# 02_IO.net
KiCad netlist of a schematic drawn in Altium Designer
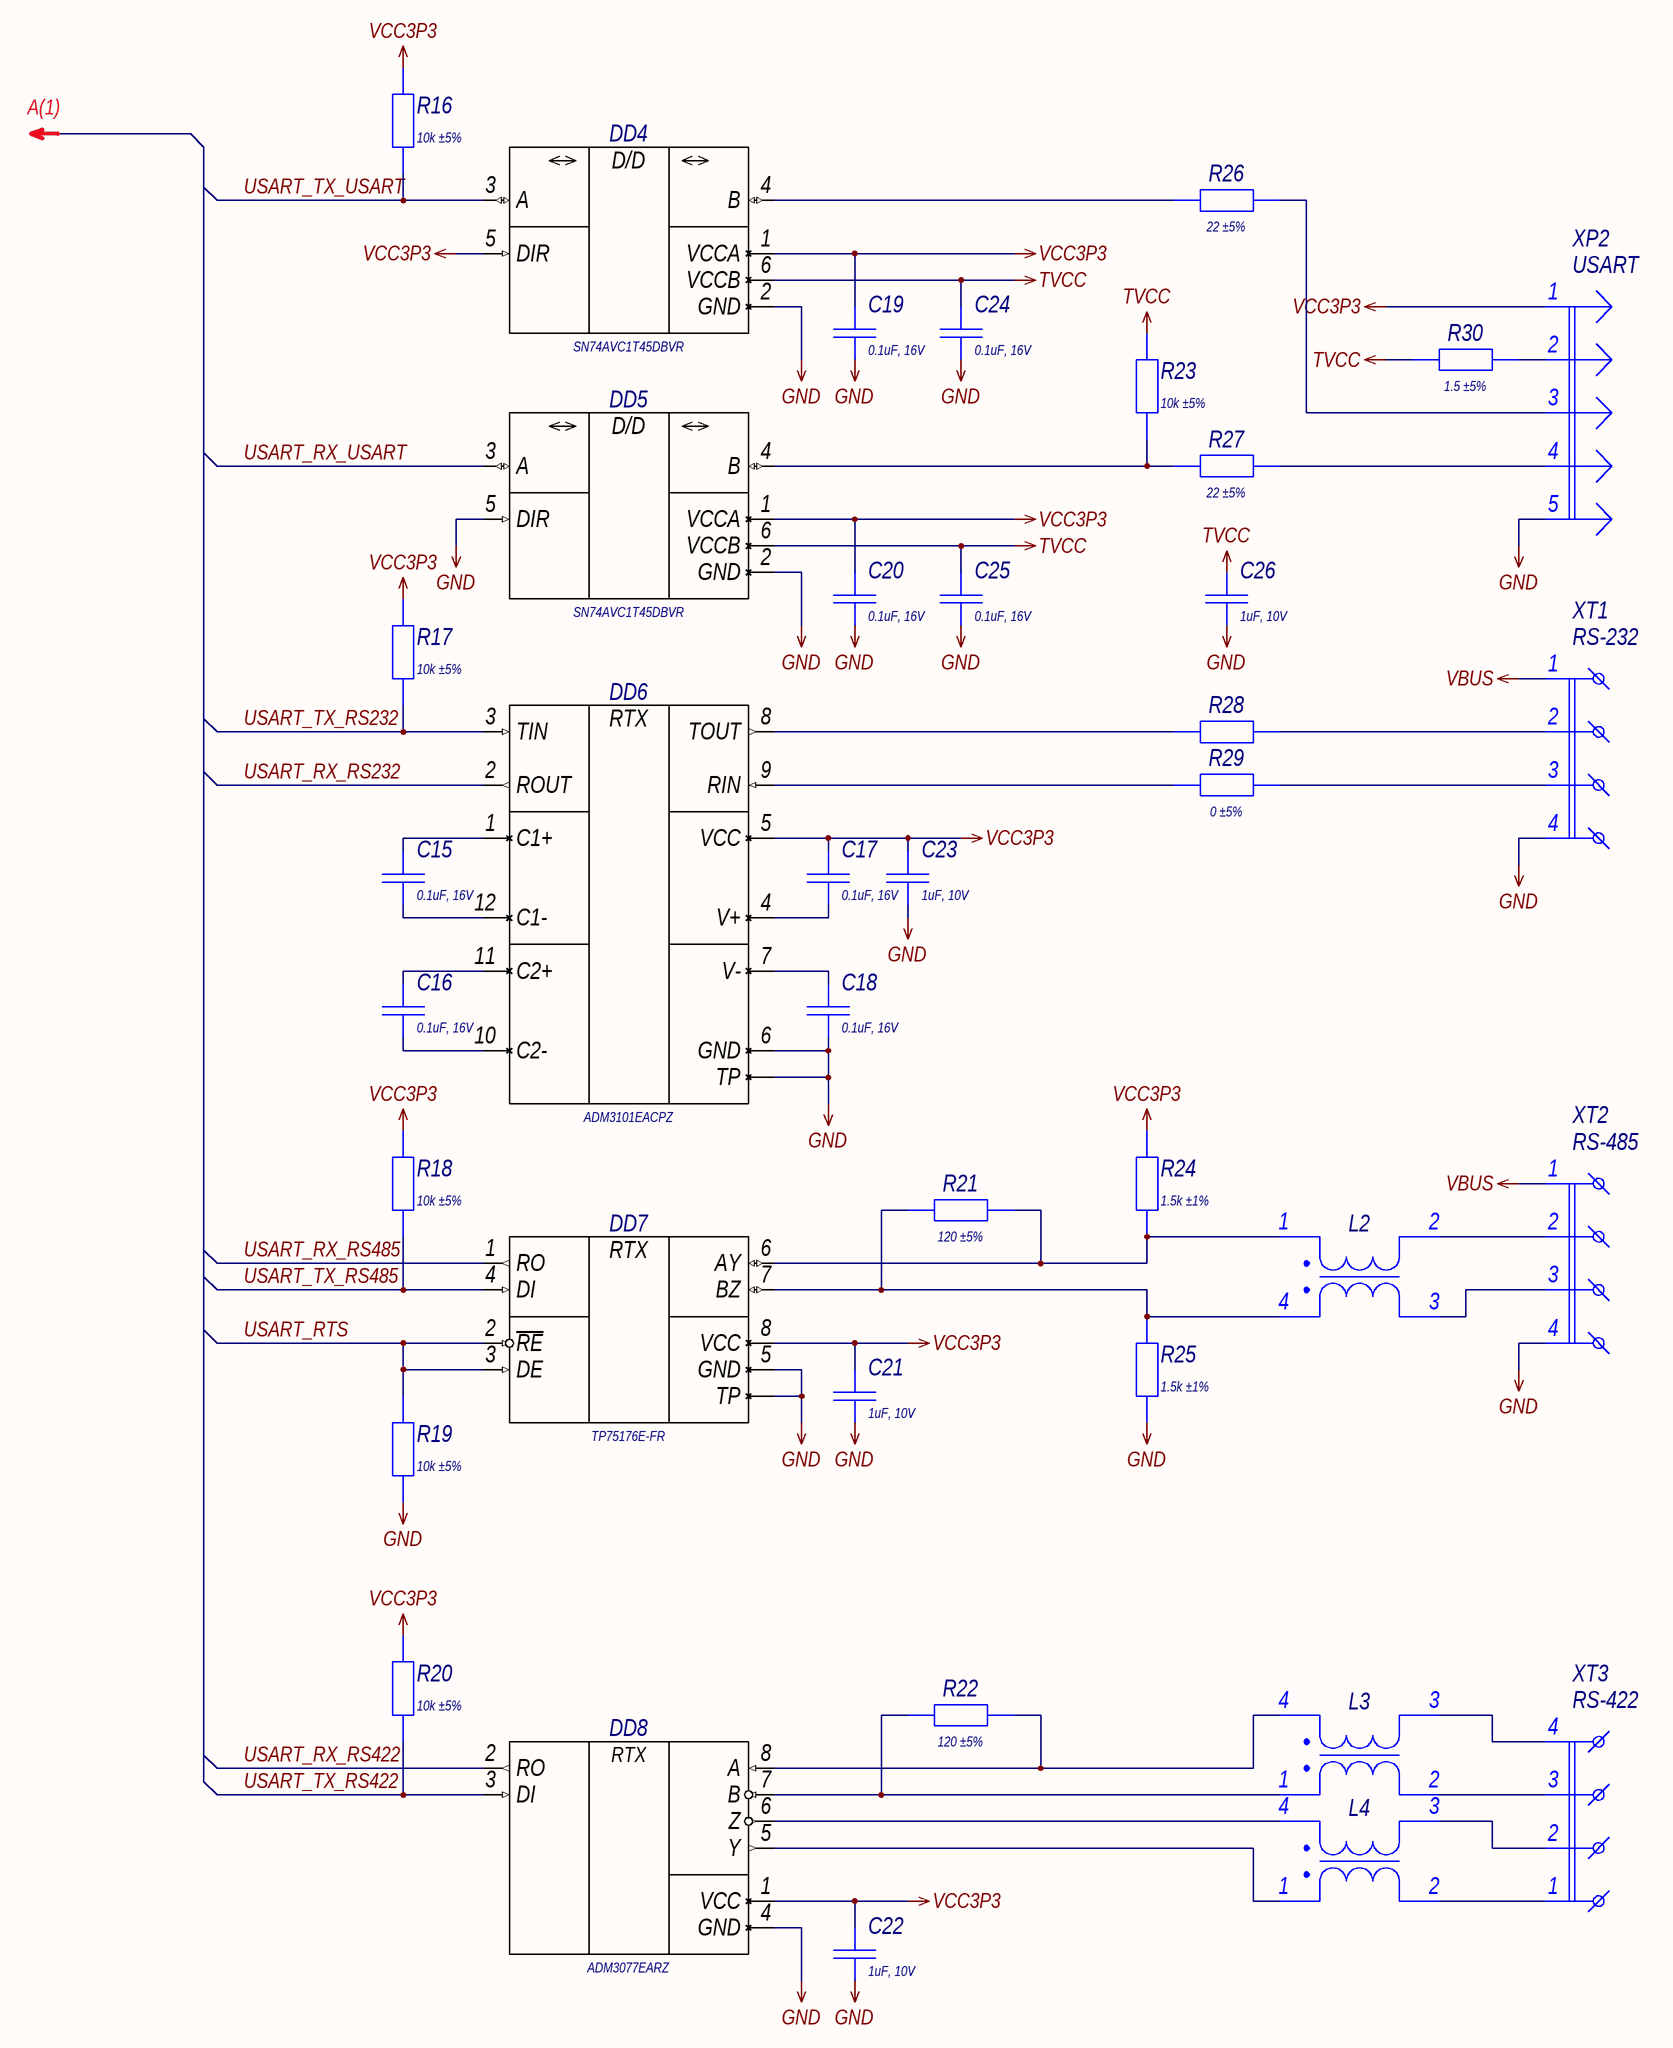
[diagram p0: 02_IO.SchDoc]

(export (version "E")
  (design (tool "Eeschema 10.0.6"))
  (components
    (comp (ref "C15")
      (value "Capacitor")
      (footprint "C0402_100X050H050_H")
      (fields
        (field (name "SCHEMATIC VALUE") "0.1uF, 16V")
        (field (name "PART NUMBER") "GCM155R71C104KA55D")
        (field (name "VOLTAGE") "16V")
        (field (name "TOLERANCE") "±10%")
        (field (name "PUBLISHER") "Andrew Danich")
      )
      (libsource (lib "ADLib") (part "Capacitor"))
    )
    (comp (ref "C16")
      (value "Capacitor")
      (footprint "C0402_100X050H050_H")
      (fields
        (field (name "SCHEMATIC VALUE") "0.1uF, 16V")
        (field (name "PART NUMBER") "GCM155R71C104KA55D")
        (field (name "VOLTAGE") "16V")
        (field (name "TOLERANCE") "±10%")
        (field (name "PUBLISHER") "Andrew Danich")
      )
      (libsource (lib "ADLib") (part "Capacitor"))
    )
    (comp (ref "C17")
      (value "Capacitor")
      (footprint "C0402_100X050H050_H")
      (fields
        (field (name "SCHEMATIC VALUE") "0.1uF, 16V")
        (field (name "PART NUMBER") "GCM155R71C104KA55D")
        (field (name "VOLTAGE") "16V")
        (field (name "TOLERANCE") "±10%")
        (field (name "PUBLISHER") "Andrew Danich")
      )
      (libsource (lib "ADLib") (part "Capacitor"))
    )
    (comp (ref "C18")
      (value "Capacitor")
      (footprint "C0402_100X050H050_H")
      (fields
        (field (name "SCHEMATIC VALUE") "0.1uF, 16V")
        (field (name "PART NUMBER") "GCM155R71C104KA55D")
        (field (name "VOLTAGE") "16V")
        (field (name "TOLERANCE") "±10%")
        (field (name "PUBLISHER") "Andrew Danich")
      )
      (libsource (lib "ADLib") (part "Capacitor"))
    )
    (comp (ref "C19")
      (value "Capacitor")
      (footprint "C0402_100X050H050_H")
      (fields
        (field (name "SCHEMATIC VALUE") "0.1uF, 16V")
        (field (name "PART NUMBER") "GCM155R71C104KA55D")
        (field (name "VOLTAGE") "16V")
        (field (name "TOLERANCE") "±10%")
        (field (name "PUBLISHER") "Andrew Danich")
      )
      (libsource (lib "ADLib") (part "Capacitor"))
    )
    (comp (ref "C20")
      (value "Capacitor")
      (footprint "C0402_100X050H050_H")
      (fields
        (field (name "SCHEMATIC VALUE") "0.1uF, 16V")
        (field (name "PART NUMBER") "GCM155R71C104KA55D")
        (field (name "VOLTAGE") "16V")
        (field (name "TOLERANCE") "±10%")
        (field (name "PUBLISHER") "Andrew Danich")
      )
      (libsource (lib "ADLib") (part "Capacitor"))
    )
    (comp (ref "C21")
      (value "Capacitor")
      (footprint "C0402_100X050H050_H")
      (fields
        (field (name "SCHEMATIC VALUE") "1uF, 10V")
        (field (name "PART NUMBER") "GRM155C71A105KE11D")
        (field (name "VOLTAGE") "10V")
        (field (name "TOLERANCE") "±10%")
        (field (name "PUBLISHER") "Andrew Danich")
      )
      (libsource (lib "ADLib") (part "Capacitor"))
    )
    (comp (ref "C22")
      (value "Capacitor")
      (footprint "C0402_100X050H050_H")
      (fields
        (field (name "SCHEMATIC VALUE") "1uF, 10V")
        (field (name "PART NUMBER") "GRM155C71A105KE11D")
        (field (name "VOLTAGE") "10V")
        (field (name "TOLERANCE") "±10%")
        (field (name "PUBLISHER") "Andrew Danich")
      )
      (libsource (lib "ADLib") (part "Capacitor"))
    )
    (comp (ref "C23")
      (value "Capacitor")
      (footprint "C0402_100X050H050_H")
      (fields
        (field (name "SCHEMATIC VALUE") "1uF, 10V")
        (field (name "PART NUMBER") "GRM155C71A105KE11D")
        (field (name "VOLTAGE") "10V")
        (field (name "TOLERANCE") "±10%")
        (field (name "PUBLISHER") "Andrew Danich")
      )
      (libsource (lib "ADLib") (part "Capacitor"))
    )
    (comp (ref "C24")
      (value "Capacitor")
      (footprint "C0402_100X050H050_H")
      (fields
        (field (name "SCHEMATIC VALUE") "0.1uF, 16V")
        (field (name "PART NUMBER") "GCM155R71C104KA55D")
        (field (name "VOLTAGE") "16V")
        (field (name "TOLERANCE") "±10%")
        (field (name "PUBLISHER") "Andrew Danich")
      )
      (libsource (lib "ADLib") (part "Capacitor"))
    )
    (comp (ref "C25")
      (value "Capacitor")
      (footprint "C0402_100X050H050_H")
      (fields
        (field (name "SCHEMATIC VALUE") "0.1uF, 16V")
        (field (name "PART NUMBER") "GCM155R71C104KA55D")
        (field (name "VOLTAGE") "16V")
        (field (name "TOLERANCE") "±10%")
        (field (name "PUBLISHER") "Andrew Danich")
      )
      (libsource (lib "ADLib") (part "Capacitor"))
    )
    (comp (ref "C26")
      (value "Capacitor")
      (footprint "C0402_100X050H050_H")
      (fields
        (field (name "SCHEMATIC VALUE") "1uF, 10V")
        (field (name "PART NUMBER") "GRM155C71A105KE11D")
        (field (name "VOLTAGE") "10V")
        (field (name "TOLERANCE") "±10%")
        (field (name "PUBLISHER") "Andrew Danich")
      )
      (libsource (lib "ADLib") (part "Capacitor"))
    )
    (comp (ref "DD4")
      (value "SN74AVC1T45Dx-Series")
      (footprint "SOT-23-6_095P290X160X145_N")
      (fields
        (field (name "SCHEMATIC VALUE") "SN74AVC1T45DBVR")
        (field (name "PART NUMBER") "SN74AVC1T45DBVR")
        (field (name "LCSC PART") "C131978")
        (field (name "MANUFACTURER") "Texas Instruments")
        (field (name "PUBLISHER") "Andrew Danich")
      )
      (libsource (lib "ADLib") (part "SN74AVC1T45Dx-Series"))
    )
    (comp (ref "DD5")
      (value "SN74AVC1T45Dx-Series")
      (footprint "SOT-23-6_095P290X160X145_N")
      (fields
        (field (name "SCHEMATIC VALUE") "SN74AVC1T45DBVR")
        (field (name "PART NUMBER") "SN74AVC1T45DBVR")
        (field (name "LCSC PART") "C131978")
        (field (name "MANUFACTURER") "Texas Instruments")
        (field (name "PUBLISHER") "Andrew Danich")
      )
      (libsource (lib "ADLib") (part "SN74AVC1T45Dx-Series"))
    )
    (comp (ref "DD6")
      (value "ADM3101EAC")
      (footprint "LFCSP-12_050P300X300X080_N")
      (fields
        (field (name "SCHEMATIC VALUE") "ADM3101EACPZ")
        (field (name "PART NUMBER") "ADM3101EACPZ")
        (field (name "MANUFACTURER") "Analog Devices")
        (field (name "PUBLISHER") "Andrew Danich")
      )
      (libsource (lib "ADLib") (part "ADM3101EAC"))
    )
    (comp (ref "DD7")
      (value "TP75176E-FR")
      (footprint "DFN-8_065P300X300X090_N")
      (fields
        (field (name "SCHEMATIC VALUE") "TP75176E-FR")
        (field (name "MANUFACTURER") "3PEAK")
        (field (name "PUBLISHER") "Andrew Danich")
      )
      (libsource (lib "ADLib") (part "TP75176E-FR"))
    )
    (comp (ref "DD8")
      (value "ADM3077")
      (footprint "SOIC-8_127P490X391X155_N")
      (fields
        (field (name "SCHEMATIC VALUE") "ADM3077EARZ")
        (field (name "PART NUMBER") "ADM3077EARZ")
        (field (name "MANUFACTURER") "Analog Devices")
        (field (name "PUBLISHER") "Andrew Danich")
      )
      (libsource (lib "ADLib") (part "ADM3077"))
    )
    (comp (ref "L2")
      (value "Coil-2xCommon_H")
      (footprint "DLW21HN-Series")
      (fields
        (field (name "PART NUMBER") "DLW21HN121SQ2L")
        (field (name "LCSC PART") "C113040")
        (field (name "MANUFACTURER") "Murata")
        (field (name "PUBLISHER") "Andrew Danich")
      )
      (libsource (lib "ADLib") (part "Coil-2xCommon_H"))
    )
    (comp (ref "L3")
      (value "Coil-2xCommon_H")
      (footprint "DLW21HN-Series")
      (fields
        (field (name "PART NUMBER") "DLW21HN121SQ2L")
        (field (name "LCSC PART") "C113040")
        (field (name "MANUFACTURER") "Murata")
        (field (name "PUBLISHER") "Andrew Danich")
      )
      (libsource (lib "") (part "Coil-2xCommon_H_1"))
    )
    (comp (ref "L4")
      (value "Coil-2xCommon_H")
      (footprint "DLW21HN-Series")
      (fields
        (field (name "PART NUMBER") "DLW21HN121SQ2L")
        (field (name "LCSC PART") "C113040")
        (field (name "MANUFACTURER") "Murata")
        (field (name "PUBLISHER") "Andrew Danich")
      )
      (libsource (lib "") (part "Coil-2xCommon_H_1"))
    )
    (comp (ref "R16")
      (value "Resistor")
      (footprint "R0402_100X050H035_H")
      (fields
        (field (name "SCHEMATIC VALUE") "10k ±5%")
        (field (name "PART NUMBER") "RC0402JR-0710KL")
        (field (name "TOLERANCE") "±5%")
        (field (name "MANUFACTURER") "Yageo")
        (field (name "PUBLISHER") "Andrew Danich")
      )
      (libsource (lib "ADLib") (part "Resistor"))
    )
    (comp (ref "R17")
      (value "Resistor")
      (footprint "R0402_100X050H035_H")
      (fields
        (field (name "SCHEMATIC VALUE") "10k ±5%")
        (field (name "PART NUMBER") "RC0402JR-0710KL")
        (field (name "TOLERANCE") "±5%")
        (field (name "MANUFACTURER") "Yageo")
        (field (name "PUBLISHER") "Andrew Danich")
      )
      (libsource (lib "ADLib") (part "Resistor"))
    )
    (comp (ref "R18")
      (value "Resistor")
      (footprint "R0402_100X050H035_H")
      (fields
        (field (name "SCHEMATIC VALUE") "10k ±5%")
        (field (name "PART NUMBER") "RC0402JR-0710KL")
        (field (name "TOLERANCE") "±5%")
        (field (name "MANUFACTURER") "Yageo")
        (field (name "PUBLISHER") "Andrew Danich")
      )
      (libsource (lib "ADLib") (part "Resistor"))
    )
    (comp (ref "R19")
      (value "Resistor")
      (footprint "R0402_100X050H035_H")
      (fields
        (field (name "SCHEMATIC VALUE") "10k ±5%")
        (field (name "PART NUMBER") "RC0402JR-0710KL")
        (field (name "TOLERANCE") "±5%")
        (field (name "MANUFACTURER") "Yageo")
        (field (name "PUBLISHER") "Andrew Danich")
      )
      (libsource (lib "ADLib") (part "Resistor"))
    )
    (comp (ref "R20")
      (value "Resistor")
      (footprint "R0402_100X050H035_H")
      (fields
        (field (name "SCHEMATIC VALUE") "10k ±5%")
        (field (name "PART NUMBER") "RC0402JR-0710KL")
        (field (name "TOLERANCE") "±5%")
        (field (name "MANUFACTURER") "Yageo")
        (field (name "PUBLISHER") "Andrew Danich")
      )
      (libsource (lib "ADLib") (part "Resistor"))
    )
    (comp (ref "R21")
      (value "Resistor")
      (footprint "R0603_160X080H045_H")
      (fields
        (field (name "SCHEMATIC VALUE") "120 ±5%")
        (field (name "PART NUMBER") "RC0603JR-07120R")
        (field (name "TOLERANCE") "±5%")
        (field (name "MANUFACTURER") "Yageo")
        (field (name "PUBLISHER") "Andrew Danich")
      )
      (libsource (lib "ADLib") (part "Resistor"))
    )
    (comp (ref "R22")
      (value "Resistor")
      (footprint "R0603_160X080H045_H")
      (fields
        (field (name "SCHEMATIC VALUE") "120 ±5%")
        (field (name "PART NUMBER") "RC0603JR-07120R")
        (field (name "TOLERANCE") "±5%")
        (field (name "MANUFACTURER") "Yageo")
        (field (name "PUBLISHER") "Andrew Danich")
      )
      (libsource (lib "ADLib") (part "Resistor"))
    )
    (comp (ref "R23")
      (value "Resistor")
      (footprint "R0402_100X050H035_H")
      (fields
        (field (name "SCHEMATIC VALUE") "10k ±5%")
        (field (name "PART NUMBER") "RC0402JR-0710KL")
        (field (name "TOLERANCE") "±5%")
        (field (name "MANUFACTURER") "Yageo")
        (field (name "PUBLISHER") "Andrew Danich")
      )
      (libsource (lib "ADLib") (part "Resistor"))
    )
    (comp (ref "R24")
      (value "Resistor")
      (footprint "R0402_100X050H035_H")
      (fields
        (field (name "SCHEMATIC VALUE") "1.5k ±1%")
        (field (name "PART NUMBER") "RC0402FR-071K5L")
        (field (name "TOLERANCE") "±1%")
        (field (name "MANUFACTURER") "Yageo")
        (field (name "PUBLISHER") "Andrew Danich")
      )
      (libsource (lib "ADLib") (part "Resistor"))
    )
    (comp (ref "R25")
      (value "Resistor")
      (footprint "R0402_100X050H035_H")
      (fields
        (field (name "SCHEMATIC VALUE") "1.5k ±1%")
        (field (name "PART NUMBER") "RC0402FR-071K5L")
        (field (name "TOLERANCE") "±1%")
        (field (name "MANUFACTURER") "Yageo")
        (field (name "PUBLISHER") "Andrew Danich")
      )
      (libsource (lib "ADLib") (part "Resistor"))
    )
    (comp (ref "R26")
      (value "Resistor")
      (footprint "R0402_100X050H035_H")
      (fields
        (field (name "SCHEMATIC VALUE") "22 ±5%")
        (field (name "PART NUMBER") "RC0402JR-0722RL")
        (field (name "TOLERANCE") "±5%")
        (field (name "MANUFACTURER") "Yageo")
        (field (name "PUBLISHER") "Andrew Danich")
      )
      (libsource (lib "ADLib") (part "Resistor"))
    )
    (comp (ref "R27")
      (value "Resistor")
      (footprint "R0402_100X050H035_H")
      (fields
        (field (name "SCHEMATIC VALUE") "22 ±5%")
        (field (name "PART NUMBER") "RC0402JR-0722RL")
        (field (name "TOLERANCE") "±5%")
        (field (name "MANUFACTURER") "Yageo")
        (field (name "PUBLISHER") "Andrew Danich")
      )
      (libsource (lib "ADLib") (part "Resistor"))
    )
    (comp (ref "R28")
      (value "Resistor")
      (footprint "R0402_100X050H035_H")
      (fields
        (field (name "PART NUMBER") "RC0402JR-070RL")
        (field (name "TOLERANCE") "±5%")
        (field (name "MANUFACTURER") "Yageo")
        (field (name "PUBLISHER") "Andrew Danich")
      )
      (libsource (lib "ADLib") (part "Resistor"))
    )
    (comp (ref "R29")
      (value "Resistor")
      (footprint "R0402_100X050H035_H")
      (fields
        (field (name "SCHEMATIC VALUE") "0 ±5%")
        (field (name "PART NUMBER") "RC0402JR-070RL")
        (field (name "TOLERANCE") "±5%")
        (field (name "MANUFACTURER") "Yageo")
        (field (name "PUBLISHER") "Andrew Danich")
      )
      (libsource (lib "ADLib") (part "Resistor"))
    )
    (comp (ref "R30")
      (value "Resistor")
      (footprint "R0402_100X050H035_H")
      (fields
        (field (name "SCHEMATIC VALUE") "1.5 ±5%")
        (field (name "PART NUMBER") "RC0402JR-071R5L")
        (field (name "TOLERANCE") "±5%")
        (field (name "MANUFACTURER") "Yageo")
        (field (name "PUBLISHER") "Andrew Danich")
      )
      (libsource (lib "ADLib") (part "Resistor"))
    )
    (comp (ref "XP2")
      (value "USART")
      (footprint "PLS-5")
      (fields (field (name "PART NUMBER") "PLS-5") (field (name "PUBLISHER") "Andrew Danich"))
      (libsource (lib "ADLib") (part "Con-5-M"))
    )
    (comp (ref "XT1")
      (value "RS-232")
      (footprint "ECH381R-04P")
      (fields
        (field (name "PART NUMBER") "ECH381R-04P")
        (field (name "MANUFACTURER") "Dinkle Enterprise")
        (field (name "PUBLISHER") "Andrew Danich")
      )
      (libsource (lib "ADLib") (part "Con-4-T"))
    )
    (comp (ref "XT2")
      (value "RS-485")
      (footprint "ECH381R-04P")
      (fields
        (field (name "PART NUMBER") "ECH381R-04P")
        (field (name "MANUFACTURER") "Dinkle Enterprise")
        (field (name "PUBLISHER") "Andrew Danich")
      )
      (libsource (lib "ADLib") (part "Con-4-T"))
    )
    (comp (ref "XT3")
      (value "RS-422")
      (footprint "ECH381R-04P")
      (fields
        (field (name "PART NUMBER") "ECH381R-04P")
        (field (name "MANUFACTURER") "Dinkle Enterprise")
        (field (name "PUBLISHER") "Andrew Danich")
      )
      (libsource (lib "ADLib") (part "Con-4-T"))
    )
  )
  (nets
    (net (code "1") (name "/USART_RTS") (class "Default")
      (node (ref "DD7") (pin "2") (pinfunction "~{RE}_2") (pintype "input"))
      (node (ref "DD7") (pin "3") (pinfunction "DE_3") (pintype "input"))
      (node (ref "R19") (pin "2") (pinfunction "2_2") (pintype "passive"))
    )
    (net (code "2") (name "/USART_RX_RS232") (class "Default")
      (node (ref "DD6") (pin "2") (pinfunction "ROUT_2") (pintype "output"))
    )
    (net (code "3") (name "/USART_RX_RS422") (class "Default")
      (node (ref "DD8") (pin "2") (pinfunction "RO_2") (pintype "output"))
    )
    (net (code "4") (name "/USART_RX_RS485") (class "Default")
      (node (ref "DD7") (pin "1") (pinfunction "RO_1") (pintype "output"))
    )
    (net (code "5") (name "/USART_RX_USART") (class "Default")
      (node (ref "DD5") (pin "3") (pinfunction "A_3") (pintype "bidirectional"))
    )
    (net (code "6") (name "/USART_TX_RS232") (class "Default")
      (node (ref "DD6") (pin "3") (pinfunction "TIN_3") (pintype "input"))
      (node (ref "R17") (pin "1") (pinfunction "1_1") (pintype "passive"))
    )
    (net (code "7") (name "/USART_TX_RS422") (class "Default")
      (node (ref "DD8") (pin "3") (pinfunction "DI_3") (pintype "input"))
      (node (ref "R20") (pin "1") (pinfunction "1_1") (pintype "passive"))
    )
    (net (code "8") (name "/USART_TX_RS485") (class "Default")
      (node (ref "DD7") (pin "4") (pinfunction "DI_4") (pintype "input"))
      (node (ref "R18") (pin "1") (pinfunction "1_1") (pintype "passive"))
    )
    (net (code "9") (name "/USART_TX_USART") (class "Default")
      (node (ref "DD4") (pin "3") (pinfunction "A_3") (pintype "bidirectional"))
      (node (ref "R16") (pin "1") (pinfunction "1_1") (pintype "passive"))
    )
    (net (code "10") (name "GND") (class "Default")
      (node (ref "C18") (pin "2") (pinfunction "2_2") (pintype "passive"))
      (node (ref "C19") (pin "2") (pinfunction "2_2") (pintype "passive"))
      (node (ref "C20") (pin "2") (pinfunction "2_2") (pintype "passive"))
      (node (ref "C21") (pin "2") (pinfunction "2_2") (pintype "passive"))
      (node (ref "C22") (pin "2") (pinfunction "2_2") (pintype "passive"))
      (node (ref "C23") (pin "2") (pinfunction "2_2") (pintype "passive"))
      (node (ref "C24") (pin "2") (pinfunction "2_2") (pintype "passive"))
      (node (ref "C25") (pin "2") (pinfunction "2_2") (pintype "passive"))
      (node (ref "C26") (pin "2") (pinfunction "2_2") (pintype "passive"))
      (node (ref "DD4") (pin "2") (pinfunction "GND_2") (pintype "power_in"))
      (node (ref "DD5") (pin "2") (pinfunction "GND_2") (pintype "power_in"))
      (node (ref "DD5") (pin "5") (pinfunction "DIR_5") (pintype "input"))
      (node (ref "DD6") (pin "6") (pinfunction "GND_6") (pintype "power_in"))
      (node (ref "DD6") (pin "TP") (pinfunction "TP_TP") (pintype "passive"))
      (node (ref "DD7") (pin "5") (pinfunction "GND_5") (pintype "power_in"))
      (node (ref "DD7") (pin "TP") (pinfunction "TP_TP") (pintype "power_in"))
      (node (ref "DD8") (pin "4") (pinfunction "GND_4") (pintype "power_in"))
      (node (ref "R19") (pin "1") (pinfunction "1_1") (pintype "passive"))
      (node (ref "R25") (pin "2") (pinfunction "2_2") (pintype "passive"))
      (node (ref "XP2") (pin "5") (pintype "passive"))
      (node (ref "XT1") (pin "4") (pintype "passive"))
      (node (ref "XT2") (pin "4") (pintype "passive"))
    )
    (net (code "11") (name "Net-(DD4-B)") (class "Default")
      (node (ref "DD4") (pin "4") (pinfunction "B_4") (pintype "bidirectional"))
      (node (ref "R26") (pin "2") (pinfunction "2_2") (pintype "passive"))
    )
    (net (code "12") (name "Net-(DD5-B)") (class "Default")
      (node (ref "DD5") (pin "4") (pinfunction "B_4") (pintype "bidirectional"))
      (node (ref "R23") (pin "1") (pinfunction "1_1") (pintype "passive"))
      (node (ref "R27") (pin "2") (pinfunction "2_2") (pintype "passive"))
    )
    (net (code "13") (name "Net-(DD6-C1+)") (class "Default")
      (node (ref "C15") (pin "1") (pinfunction "1_1") (pintype "passive"))
      (node (ref "DD6") (pin "1") (pinfunction "C1+_1") (pintype "passive"))
    )
    (net (code "14") (name "Net-(DD6-C1-)") (class "Default")
      (node (ref "C15") (pin "2") (pinfunction "2_2") (pintype "passive"))
      (node (ref "DD6") (pin "12") (pinfunction "C1-_12") (pintype "passive"))
    )
    (net (code "15") (name "Net-(DD6-C2+)") (class "Default")
      (node (ref "C16") (pin "1") (pinfunction "1_1") (pintype "passive"))
      (node (ref "DD6") (pin "11") (pinfunction "C2+_11") (pintype "passive"))
    )
    (net (code "16") (name "Net-(DD6-C2-)") (class "Default")
      (node (ref "C16") (pin "2") (pinfunction "2_2") (pintype "passive"))
      (node (ref "DD6") (pin "10") (pinfunction "C2-_10") (pintype "passive"))
    )
    (net (code "17") (name "Net-(DD6-RIN)") (class "Default")
      (node (ref "DD6") (pin "9") (pinfunction "RIN_9") (pintype "input"))
      (node (ref "R29") (pin "2") (pinfunction "2_2") (pintype "passive"))
    )
    (net (code "18") (name "Net-(DD6-TOUT)") (class "Default")
      (node (ref "DD6") (pin "8") (pinfunction "TOUT_8") (pintype "output"))
      (node (ref "R28") (pin "2") (pinfunction "2_2") (pintype "passive"))
    )
    (net (code "19") (name "Net-(DD6-V+)") (class "Default")
      (node (ref "C17") (pin "2") (pinfunction "2_2") (pintype "passive"))
      (node (ref "DD6") (pin "4") (pinfunction "V+_4") (pintype "passive"))
    )
    (net (code "20") (name "Net-(DD6-V-)") (class "Default")
      (node (ref "C18") (pin "1") (pinfunction "1_1") (pintype "passive"))
      (node (ref "DD6") (pin "7") (pinfunction "V-_7") (pintype "passive"))
    )
    (net (code "21") (name "Net-(DD7-AY)") (class "Default")
      (node (ref "DD7") (pin "6") (pinfunction "AY_6") (pintype "bidirectional"))
      (node (ref "L2") (pin "1") (pinfunction "1_1") (pintype "passive"))
      (node (ref "R21") (pin "2") (pinfunction "2_2") (pintype "passive"))
      (node (ref "R24") (pin "2") (pinfunction "2_2") (pintype "passive"))
    )
    (net (code "22") (name "Net-(DD7-BZ)") (class "Default")
      (node (ref "DD7") (pin "7") (pinfunction "BZ_7") (pintype "bidirectional"))
      (node (ref "L2") (pin "4") (pinfunction "4_4") (pintype "passive"))
      (node (ref "R21") (pin "1") (pinfunction "1_1") (pintype "passive"))
      (node (ref "R25") (pin "1") (pinfunction "1_1") (pintype "passive"))
    )
    (net (code "23") (name "Net-(DD8-A)") (class "Default")
      (node (ref "DD8") (pin "8") (pinfunction "A_8") (pintype "input"))
      (node (ref "L3") (pin "4") (pinfunction "4_4") (pintype "passive"))
      (node (ref "R22") (pin "2") (pinfunction "2_2") (pintype "passive"))
    )
    (net (code "24") (name "Net-(DD8-B)") (class "Default")
      (node (ref "DD8") (pin "7") (pinfunction "B_7") (pintype "input"))
      (node (ref "L3") (pin "1") (pinfunction "1_1") (pintype "passive"))
      (node (ref "R22") (pin "1") (pinfunction "1_1") (pintype "passive"))
    )
    (net (code "25") (name "Net-(DD8-Y)") (class "Default")
      (node (ref "DD8") (pin "5") (pinfunction "Y_5") (pintype "output"))
      (node (ref "L4") (pin "1") (pinfunction "1_1") (pintype "passive"))
    )
    (net (code "26") (name "Net-(DD8-Z)") (class "Default")
      (node (ref "DD8") (pin "6") (pinfunction "Z_6") (pintype "output"))
      (node (ref "L4") (pin "4") (pinfunction "4_4") (pintype "passive"))
    )
    (net (code "27") (name "Net-(L2-Pad2)") (class "Default")
      (node (ref "L2") (pin "2") (pinfunction "2_2") (pintype "passive"))
      (node (ref "XT2") (pin "2") (pintype "passive"))
    )
    (net (code "28") (name "Net-(L2-Pad3)") (class "Default")
      (node (ref "L2") (pin "3") (pinfunction "3_3") (pintype "passive"))
      (node (ref "XT2") (pin "3") (pintype "passive"))
    )
    (net (code "29") (name "Net-(L3-Pad2)") (class "Default")
      (node (ref "L3") (pin "2") (pinfunction "2_2") (pintype "passive"))
      (node (ref "XT3") (pin "3") (pintype "passive"))
    )
    (net (code "30") (name "Net-(L3-Pad3)") (class "Default")
      (node (ref "L3") (pin "3") (pinfunction "3_3") (pintype "passive"))
      (node (ref "XT3") (pin "4") (pintype "passive"))
    )
    (net (code "31") (name "Net-(L4-Pad2)") (class "Default")
      (node (ref "L4") (pin "2") (pinfunction "2_2") (pintype "passive"))
      (node (ref "XT3") (pin "1") (pintype "passive"))
    )
    (net (code "32") (name "Net-(L4-Pad3)") (class "Default")
      (node (ref "L4") (pin "3") (pinfunction "3_3") (pintype "passive"))
      (node (ref "XT3") (pin "2") (pintype "passive"))
    )
    (net (code "33") (name "Net-(R26-Pad1)") (class "Default")
      (node (ref "R26") (pin "1") (pinfunction "1_1") (pintype "passive"))
      (node (ref "XP2") (pin "3") (pintype "passive"))
    )
    (net (code "34") (name "Net-(R27-Pad1)") (class "Default")
      (node (ref "R27") (pin "1") (pinfunction "1_1") (pintype "passive"))
      (node (ref "XP2") (pin "4") (pintype "passive"))
    )
    (net (code "35") (name "Net-(R28-Pad1)") (class "Default")
      (node (ref "R28") (pin "1") (pinfunction "1_1") (pintype "passive"))
      (node (ref "XT1") (pin "2") (pintype "passive"))
    )
    (net (code "36") (name "Net-(R29-Pad1)") (class "Default")
      (node (ref "R29") (pin "1") (pinfunction "1_1") (pintype "passive"))
      (node (ref "XT1") (pin "3") (pintype "passive"))
    )
    (net (code "37") (name "Net-(R30-Pad1)") (class "Default")
      (node (ref "R30") (pin "1") (pinfunction "1_1") (pintype "passive"))
      (node (ref "XP2") (pin "2") (pintype "passive"))
    )
    (net (code "38") (name "TVCC") (class "Default")
      (node (ref "C24") (pin "1") (pinfunction "1_1") (pintype "passive"))
      (node (ref "C25") (pin "1") (pinfunction "1_1") (pintype "passive"))
      (node (ref "C26") (pin "1") (pinfunction "1_1") (pintype "passive"))
      (node (ref "DD4") (pin "6") (pinfunction "VCCB_6") (pintype "power_in"))
      (node (ref "DD5") (pin "6") (pinfunction "VCCB_6") (pintype "power_in"))
      (node (ref "R23") (pin "2") (pinfunction "2_2") (pintype "passive"))
      (node (ref "R30") (pin "2") (pinfunction "2_2") (pintype "passive"))
    )
    (net (code "39") (name "VBUS") (class "Default")
      (node (ref "XT1") (pin "1") (pintype "passive"))
      (node (ref "XT2") (pin "1") (pintype "passive"))
    )
    (net (code "40") (name "VCC3P3") (class "Default")
      (node (ref "C17") (pin "1") (pinfunction "1_1") (pintype "passive"))
      (node (ref "C19") (pin "1") (pinfunction "1_1") (pintype "passive"))
      (node (ref "C20") (pin "1") (pinfunction "1_1") (pintype "passive"))
      (node (ref "C21") (pin "1") (pinfunction "1_1") (pintype "passive"))
      (node (ref "C22") (pin "1") (pinfunction "1_1") (pintype "passive"))
      (node (ref "C23") (pin "1") (pinfunction "1_1") (pintype "passive"))
      (node (ref "DD4") (pin "1") (pinfunction "VCCA_1") (pintype "power_in"))
      (node (ref "DD4") (pin "5") (pinfunction "DIR_5") (pintype "input"))
      (node (ref "DD5") (pin "1") (pinfunction "VCCA_1") (pintype "power_in"))
      (node (ref "DD6") (pin "5") (pinfunction "VCC_5") (pintype "power_in"))
      (node (ref "DD7") (pin "8") (pinfunction "VCC_8") (pintype "power_in"))
      (node (ref "DD8") (pin "1") (pinfunction "VCC_1") (pintype "power_in"))
      (node (ref "R16") (pin "2") (pinfunction "2_2") (pintype "passive"))
      (node (ref "R17") (pin "2") (pinfunction "2_2") (pintype "passive"))
      (node (ref "R18") (pin "2") (pinfunction "2_2") (pintype "passive"))
      (node (ref "R20") (pin "2") (pinfunction "2_2") (pintype "passive"))
      (node (ref "R24") (pin "1") (pinfunction "1_1") (pintype "passive"))
      (node (ref "XP2") (pin "1") (pintype "passive"))
    )
  )
)
